# RF_SCH1.net
KiCad netlist of a schematic drawn in Altium Designer
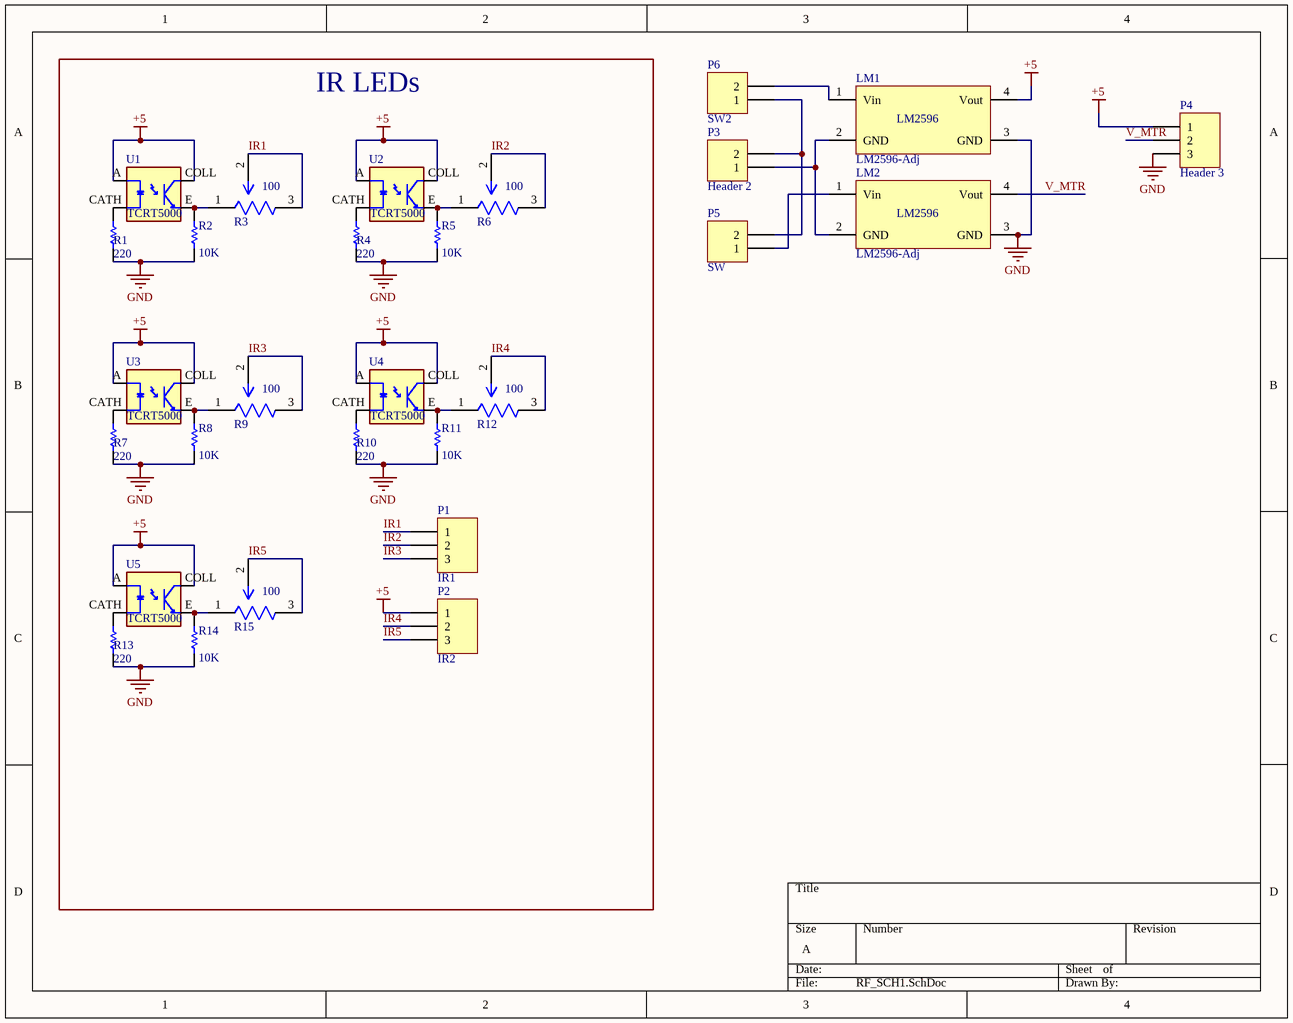
[diagram p0: RF_SCH1.SchDoc]

(export (version "E")
  (design (tool "Eeschema 10.0.6"))
  (components
    (comp (ref "LM1")
      (value "LM2596-Adj")
      (footprint "lm2596")
      (description "Designed By @Alixahedi")
      (libsource (lib "LM2596-Adj") (part "LM2596-Adj"))
    )
    (comp (ref "LM2")
      (value "LM2596-Adj")
      (footprint "lm2596")
      (description "Designed By @Alixahedi")
      (libsource (lib "LM2596-Adj") (part "LM2596-Adj"))
    )
    (comp (ref "P1")
      (value "IR1")
      (footprint "HDR1X3")
      (description "Header, 3-Pin")
      (fields (field (name "PUBLISHER") "Altium Limited"))
      (libsource (lib "Miscellaneous Connectors") (part "Header 3"))
    )
    (comp (ref "P2")
      (value "IR2")
      (footprint "HDR1X3")
      (description "Header, 3-Pin")
      (fields (field (name "PUBLISHER") "Altium Limited"))
      (libsource (lib "Miscellaneous Connectors") (part "Header 3"))
    )
    (comp (ref "P3")
      (value "Header 2")
      (footprint "HDR1X2")
      (description "Header, 2-Pin")
      (fields (field (name "PUBLISHER") "Altium Limited"))
      (libsource (lib "Miscellaneous Connectors") (part "Header 2"))
    )
    (comp (ref "P4")
      (value "Header 3")
      (footprint "HDR1X3")
      (description "Header, 3-Pin")
      (fields (field (name "PUBLISHER") "Altium Limited"))
      (libsource (lib "Miscellaneous Connectors") (part "Header 3"))
    )
    (comp (ref "P5")
      (value "SW")
      (footprint "HDR1X2")
      (description "Header, 2-Pin")
      (fields (field (name "PUBLISHER") "Altium Limited"))
      (libsource (lib "Miscellaneous Connectors") (part "Header 2"))
    )
    (comp (ref "P6")
      (value "SW2")
      (footprint "HDR1X2")
      (description "Header, 2-Pin")
      (fields (field (name "PUBLISHER") "Altium Limited"))
      (libsource (lib "Miscellaneous Connectors") (part "Header 2"))
    )
    (comp (ref "R1")
      (value "220")
      (footprint "AXIAL-0.3")
      (description "Resistor")
      (fields (field (name "Comment") "Res1") (field (name "PUBLISHER") "Altium Limited"))
      (libsource (lib "Miscellaneous Devices") (part "Res1"))
    )
    (comp (ref "R2")
      (value "10K")
      (footprint "AXIAL-0.3")
      (description "Resistor")
      (fields (field (name "Comment") "Res1") (field (name "PUBLISHER") "Altium Limited"))
      (libsource (lib "Miscellaneous Devices") (part "Res1"))
    )
    (comp (ref "R3")
      (value "100")
      (footprint "FP-3386F-MFG")
      (description "TRIMMER 30K OHM 0.5W PC PIN TOP")
      (fields (field (name "TOLERANCE") "10%") (field (name "MANUFACTURER PART NUMBER") "3386F-1-303LF"))
      (libsource (lib "Altium Content Vault") (part "f696fc322aeaec4039820165aa0401c"))
    )
    (comp (ref "R4")
      (value "220")
      (footprint "AXIAL-0.3")
      (description "Resistor")
      (fields (field (name "Comment") "Res1") (field (name "PUBLISHER") "Altium Limited"))
      (libsource (lib "Miscellaneous Devices") (part "Res1"))
    )
    (comp (ref "R5")
      (value "10K")
      (footprint "AXIAL-0.3")
      (description "Resistor")
      (fields (field (name "Comment") "Res1") (field (name "PUBLISHER") "Altium Limited"))
      (libsource (lib "Miscellaneous Devices") (part "Res1"))
    )
    (comp (ref "R6")
      (value "100")
      (footprint "FP-3386F-MFG")
      (description "TRIMMER 30K OHM 0.5W PC PIN TOP")
      (fields (field (name "TOLERANCE") "10%") (field (name "MANUFACTURER PART NUMBER") "3386F-1-303LF"))
      (libsource (lib "Altium Content Vault") (part "f696fc322aeaec4039820165aa0401c"))
    )
    (comp (ref "R7")
      (value "220")
      (footprint "AXIAL-0.3")
      (description "Resistor")
      (fields (field (name "Comment") "Res1") (field (name "PUBLISHER") "Altium Limited"))
      (libsource (lib "Miscellaneous Devices") (part "Res1"))
    )
    (comp (ref "R8")
      (value "10K")
      (footprint "AXIAL-0.3")
      (description "Resistor")
      (fields (field (name "Comment") "Res1") (field (name "PUBLISHER") "Altium Limited"))
      (libsource (lib "Miscellaneous Devices") (part "Res1"))
    )
    (comp (ref "R9")
      (value "100")
      (footprint "FP-3386F-MFG")
      (description "TRIMMER 30K OHM 0.5W PC PIN TOP")
      (fields (field (name "TOLERANCE") "10%") (field (name "MANUFACTURER PART NUMBER") "3386F-1-303LF"))
      (libsource (lib "Altium Content Vault") (part "f696fc322aeaec4039820165aa0401c"))
    )
    (comp (ref "R10")
      (value "220")
      (footprint "AXIAL-0.3")
      (description "Resistor")
      (fields (field (name "Comment") "Res1") (field (name "PUBLISHER") "Altium Limited"))
      (libsource (lib "Miscellaneous Devices") (part "Res1"))
    )
    (comp (ref "R11")
      (value "10K")
      (footprint "AXIAL-0.3")
      (description "Resistor")
      (fields (field (name "Comment") "Res1") (field (name "PUBLISHER") "Altium Limited"))
      (libsource (lib "Miscellaneous Devices") (part "Res1"))
    )
    (comp (ref "R12")
      (value "100")
      (footprint "FP-3386F-MFG")
      (description "TRIMMER 30K OHM 0.5W PC PIN TOP")
      (fields (field (name "TOLERANCE") "10%") (field (name "MANUFACTURER PART NUMBER") "3386F-1-303LF"))
      (libsource (lib "Altium Content Vault") (part "f696fc322aeaec4039820165aa0401c"))
    )
    (comp (ref "R13")
      (value "220")
      (footprint "AXIAL-0.3")
      (description "Resistor")
      (fields (field (name "Comment") "Res1") (field (name "PUBLISHER") "Altium Limited"))
      (libsource (lib "Miscellaneous Devices") (part "Res1"))
    )
    (comp (ref "R14")
      (value "10K")
      (footprint "AXIAL-0.3")
      (description "Resistor")
      (fields (field (name "Comment") "Res1") (field (name "PUBLISHER") "Altium Limited"))
      (libsource (lib "Miscellaneous Devices") (part "Res1"))
    )
    (comp (ref "R15")
      (value "100")
      (footprint "FP-3386F-MFG")
      (description "TRIMMER 30K OHM 0.5W PC PIN TOP")
      (fields (field (name "TOLERANCE") "10%") (field (name "MANUFACTURER PART NUMBER") "3386F-1-303LF"))
      (libsource (lib "Altium Content Vault") (part "f696fc322aeaec4039820165aa0401c"))
    )
    (comp (ref "U1")
      (value "TCRT5000")
      (footprint "OPTO_TCRT5000")
      (description "950 nm 60 mA Through Hole Reflective Optical Sensor with Transistor Output")
      (libsource (lib "TCRT5000") (part "TCRT5000"))
    )
    (comp (ref "U2")
      (value "TCRT5000")
      (footprint "OPTO_TCRT5000")
      (description "950 nm 60 mA Through Hole Reflective Optical Sensor with Transistor Output")
      (libsource (lib "TCRT5000") (part "TCRT5000"))
    )
    (comp (ref "U3")
      (value "TCRT5000")
      (footprint "OPTO_TCRT5000")
      (description "950 nm 60 mA Through Hole Reflective Optical Sensor with Transistor Output")
      (libsource (lib "TCRT5000") (part "TCRT5000"))
    )
    (comp (ref "U4")
      (value "TCRT5000")
      (footprint "OPTO_TCRT5000")
      (description "950 nm 60 mA Through Hole Reflective Optical Sensor with Transistor Output")
      (libsource (lib "TCRT5000") (part "TCRT5000"))
    )
    (comp (ref "U5")
      (value "TCRT5000")
      (footprint "OPTO_TCRT5000")
      (description "950 nm 60 mA Through Hole Reflective Optical Sensor with Transistor Output")
      (libsource (lib "TCRT5000") (part "TCRT5000"))
    )
  )
  (nets
    (net (code "1") (name "+5") (class "Default")
      (node (ref "LM1") (pin "4") (pinfunction "Vout_4") (pintype "passive"))
      (node (ref "P2") (pin "1") (pinfunction "1_1") (pintype "passive"))
      (node (ref "P4") (pin "1") (pinfunction "1_1") (pintype "passive"))
      (node (ref "U1") (pin "A") (pinfunction "A_A") (pintype "passive"))
      (node (ref "U1") (pin "COLL") (pinfunction "COLL_COLL") (pintype "passive"))
      (node (ref "U2") (pin "A") (pinfunction "A_A") (pintype "passive"))
      (node (ref "U2") (pin "COLL") (pinfunction "COLL_COLL") (pintype "passive"))
      (node (ref "U3") (pin "A") (pinfunction "A_A") (pintype "passive"))
      (node (ref "U3") (pin "COLL") (pinfunction "COLL_COLL") (pintype "passive"))
      (node (ref "U4") (pin "A") (pinfunction "A_A") (pintype "passive"))
      (node (ref "U4") (pin "COLL") (pinfunction "COLL_COLL") (pintype "passive"))
      (node (ref "U5") (pin "A") (pinfunction "A_A") (pintype "passive"))
      (node (ref "U5") (pin "COLL") (pinfunction "COLL_COLL") (pintype "passive"))
    )
    (net (code "2") (name "/IR1") (class "Default")
      (node (ref "P1") (pin "1") (pinfunction "1_1") (pintype "passive"))
      (node (ref "R3") (pin "2") (pinfunction "WIPER_2") (pintype "passive"))
      (node (ref "R3") (pin "3") (pinfunction "CW_3") (pintype "passive"))
    )
    (net (code "3") (name "/IR2") (class "Default")
      (node (ref "P1") (pin "2") (pinfunction "2_2") (pintype "passive"))
      (node (ref "R6") (pin "2") (pinfunction "WIPER_2") (pintype "passive"))
      (node (ref "R6") (pin "3") (pinfunction "CW_3") (pintype "passive"))
    )
    (net (code "4") (name "/IR3") (class "Default")
      (node (ref "P1") (pin "3") (pinfunction "3_3") (pintype "passive"))
      (node (ref "R9") (pin "2") (pinfunction "WIPER_2") (pintype "passive"))
      (node (ref "R9") (pin "3") (pinfunction "CW_3") (pintype "passive"))
    )
    (net (code "5") (name "/IR4") (class "Default")
      (node (ref "P2") (pin "2") (pinfunction "2_2") (pintype "passive"))
      (node (ref "R12") (pin "2") (pinfunction "WIPER_2") (pintype "passive"))
      (node (ref "R12") (pin "3") (pinfunction "CW_3") (pintype "passive"))
    )
    (net (code "6") (name "/IR5") (class "Default")
      (node (ref "P2") (pin "3") (pinfunction "3_3") (pintype "passive"))
      (node (ref "R15") (pin "2") (pinfunction "WIPER_2") (pintype "passive"))
      (node (ref "R15") (pin "3") (pinfunction "CW_3") (pintype "passive"))
    )
    (net (code "7") (name "/V_MTR") (class "Default")
      (node (ref "LM2") (pin "4") (pinfunction "Vout_4") (pintype "passive"))
      (node (ref "P4") (pin "2") (pinfunction "2_2") (pintype "passive"))
    )
    (net (code "8") (name "GND") (class "Default")
      (node (ref "LM1") (pin "3") (pinfunction "GND_3") (pintype "passive"))
      (node (ref "LM2") (pin "3") (pinfunction "GND_3") (pintype "passive"))
      (node (ref "P4") (pin "3") (pinfunction "3_3") (pintype "passive"))
      (node (ref "R1") (pin "1") (pinfunction "1_1") (pintype "passive"))
      (node (ref "R10") (pin "1") (pinfunction "1_1") (pintype "passive"))
      (node (ref "R11") (pin "1") (pinfunction "1_1") (pintype "passive"))
      (node (ref "R13") (pin "1") (pinfunction "1_1") (pintype "passive"))
      (node (ref "R14") (pin "1") (pinfunction "1_1") (pintype "passive"))
      (node (ref "R2") (pin "1") (pinfunction "1_1") (pintype "passive"))
      (node (ref "R4") (pin "1") (pinfunction "1_1") (pintype "passive"))
      (node (ref "R5") (pin "1") (pinfunction "1_1") (pintype "passive"))
      (node (ref "R7") (pin "1") (pinfunction "1_1") (pintype "passive"))
      (node (ref "R8") (pin "1") (pinfunction "1_1") (pintype "passive"))
    )
    (net (code "9") (name "Net-(LM1-GND-Pad2)") (class "Default")
      (node (ref "LM1") (pin "2") (pinfunction "GND_2") (pintype "passive"))
      (node (ref "LM2") (pin "2") (pinfunction "GND_2") (pintype "passive"))
      (node (ref "P3") (pin "1") (pinfunction "1_1") (pintype "passive"))
    )
    (net (code "10") (name "Net-(LM1-Vin)") (class "Default")
      (node (ref "LM1") (pin "1") (pinfunction "Vin_1") (pintype "passive"))
      (node (ref "P6") (pin "2") (pinfunction "2_2") (pintype "passive"))
    )
    (net (code "11") (name "Net-(LM2-Vin)") (class "Default")
      (node (ref "LM2") (pin "1") (pinfunction "Vin_1") (pintype "passive"))
      (node (ref "P5") (pin "1") (pinfunction "1_1") (pintype "passive"))
    )
    (net (code "12") (name "Net-(P3-Pad2)") (class "Default")
      (node (ref "P3") (pin "2") (pinfunction "2_2") (pintype "passive"))
      (node (ref "P5") (pin "2") (pinfunction "2_2") (pintype "passive"))
      (node (ref "P6") (pin "1") (pinfunction "1_1") (pintype "passive"))
    )
    (net (code "13") (name "Net-(R1-Pad2)") (class "Default")
      (node (ref "R1") (pin "2") (pinfunction "2_2") (pintype "passive"))
      (node (ref "U1") (pin "CATH") (pinfunction "CATH_CATH") (pintype "passive"))
    )
    (net (code "14") (name "Net-(R3-CCW)") (class "Default")
      (node (ref "R2") (pin "2") (pinfunction "2_2") (pintype "passive"))
      (node (ref "R3") (pin "1") (pinfunction "CCW_1") (pintype "passive"))
      (node (ref "U1") (pin "E") (pinfunction "E_E") (pintype "passive"))
    )
    (net (code "15") (name "Net-(R4-Pad2)") (class "Default")
      (node (ref "R4") (pin "2") (pinfunction "2_2") (pintype "passive"))
      (node (ref "U2") (pin "CATH") (pinfunction "CATH_CATH") (pintype "passive"))
    )
    (net (code "16") (name "Net-(R6-CCW)") (class "Default")
      (node (ref "R5") (pin "2") (pinfunction "2_2") (pintype "passive"))
      (node (ref "R6") (pin "1") (pinfunction "CCW_1") (pintype "passive"))
      (node (ref "U2") (pin "E") (pinfunction "E_E") (pintype "passive"))
    )
    (net (code "17") (name "Net-(R7-Pad2)") (class "Default")
      (node (ref "R7") (pin "2") (pinfunction "2_2") (pintype "passive"))
      (node (ref "U3") (pin "CATH") (pinfunction "CATH_CATH") (pintype "passive"))
    )
    (net (code "18") (name "Net-(R9-CCW)") (class "Default")
      (node (ref "R8") (pin "2") (pinfunction "2_2") (pintype "passive"))
      (node (ref "R9") (pin "1") (pinfunction "CCW_1") (pintype "passive"))
      (node (ref "U3") (pin "E") (pinfunction "E_E") (pintype "passive"))
    )
    (net (code "19") (name "Net-(R10-Pad2)") (class "Default")
      (node (ref "R10") (pin "2") (pinfunction "2_2") (pintype "passive"))
      (node (ref "U4") (pin "CATH") (pinfunction "CATH_CATH") (pintype "passive"))
    )
    (net (code "20") (name "Net-(R12-CCW)") (class "Default")
      (node (ref "R11") (pin "2") (pinfunction "2_2") (pintype "passive"))
      (node (ref "R12") (pin "1") (pinfunction "CCW_1") (pintype "passive"))
      (node (ref "U4") (pin "E") (pinfunction "E_E") (pintype "passive"))
    )
    (net (code "21") (name "Net-(R13-Pad2)") (class "Default")
      (node (ref "R13") (pin "2") (pinfunction "2_2") (pintype "passive"))
      (node (ref "U5") (pin "CATH") (pinfunction "CATH_CATH") (pintype "passive"))
    )
    (net (code "22") (name "Net-(R15-CCW)") (class "Default")
      (node (ref "R14") (pin "2") (pinfunction "2_2") (pintype "passive"))
      (node (ref "R15") (pin "1") (pinfunction "CCW_1") (pintype "passive"))
      (node (ref "U5") (pin "E") (pinfunction "E_E") (pintype "passive"))
    )
  )
)
